# Input.net
KiCad netlist of a schematic drawn in Altium Designer
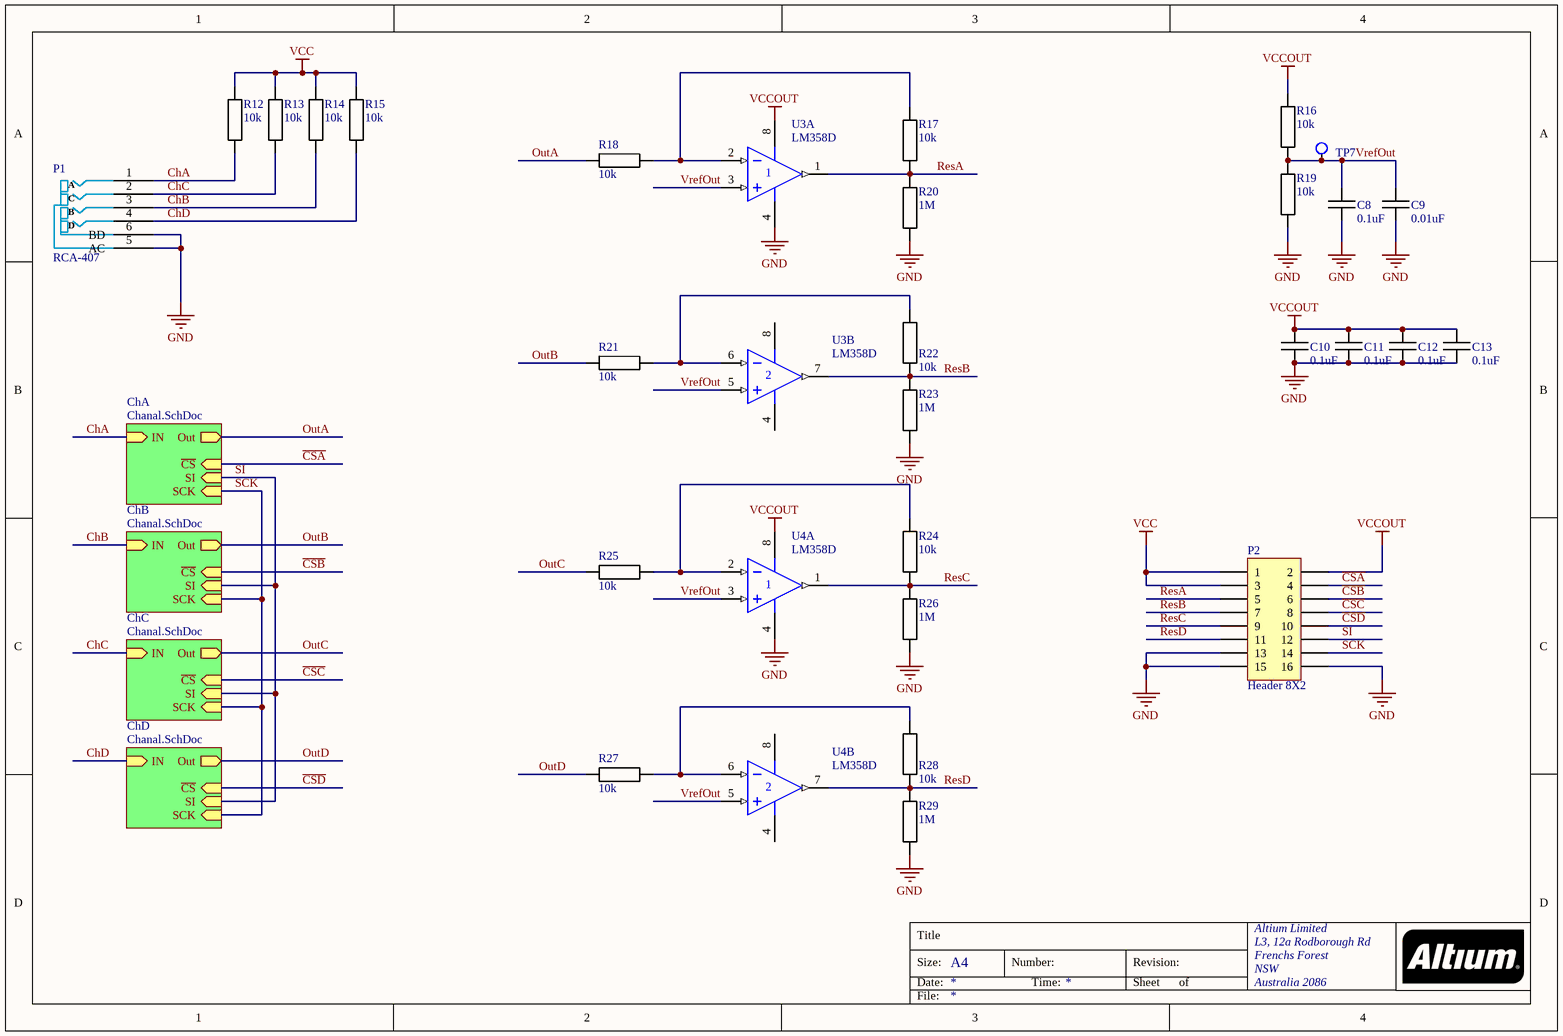
[diagram p0: Input.SchDoc]

(export (version "E")
  (design (tool "Eeschema 10.0.6"))
  (components
    (comp (ref "C8") (value "0.1uF") (footprint "SMD 0603") (libsource (lib "Maks_lib") (part "Capasitor")))
    (comp (ref "C9") (value "0.01uF") (footprint "SMD 0603") (libsource (lib "Maks_lib") (part "Capasitor")))
    (comp (ref "C10") (value "0.1uF") (footprint "SMD 0603") (libsource (lib "Maks_lib") (part "Capasitor")))
    (comp (ref "C11") (value "0.1uF") (footprint "SMD 0603") (libsource (lib "Maks_lib") (part "Capasitor")))
    (comp (ref "C12") (value "0.1uF") (footprint "SMD 0603") (libsource (lib "Maks_lib") (part "Capasitor")))
    (comp (ref "C13") (value "0.1uF") (footprint "SMD 0603") (libsource (lib "Maks_lib") (part "Capasitor")))
    (comp (ref "P1")
      (value "RCA-407")
      (footprint "RCA4")
      (description "RCA 2x2")
      (libsource (lib "Maks_lib") (part "RCA-407"))
    )
    (comp (ref "P2")
      (value "Header 8X2")
      (footprint "HDR2X8")
      (description "Header, 8-Pin, Dual row")
      (fields (field (name "PUBLISHER") "Altium Limited"))
      (libsource (lib "Miscellaneous Connectors") (part "Header 8X2"))
    )
    (comp (ref "R12") (value "10k") (footprint "SMD 0603") (libsource (lib "Maks_lib") (part "Resistor")))
    (comp (ref "R13") (value "10k") (footprint "SMD 0603") (libsource (lib "Maks_lib") (part "Resistor")))
    (comp (ref "R14") (value "10k") (footprint "SMD 0603") (libsource (lib "Maks_lib") (part "Resistor")))
    (comp (ref "R15") (value "10k") (footprint "SMD 0603") (libsource (lib "Maks_lib") (part "Resistor")))
    (comp (ref "R16") (value "10k") (footprint "SMD 0603") (libsource (lib "Maks_lib") (part "Resistor")))
    (comp (ref "R17") (value "10k") (footprint "SMD 0603") (libsource (lib "Maks_lib") (part "Resistor")))
    (comp (ref "R18") (value "10k") (footprint "SMD 0603") (libsource (lib "Maks_lib") (part "Resistor")))
    (comp (ref "R19") (value "10k") (footprint "SMD 0603") (libsource (lib "Maks_lib") (part "Resistor")))
    (comp (ref "R20") (value "1M") (footprint "SMD 0603") (libsource (lib "Maks_lib") (part "Resistor")))
    (comp (ref "R21") (value "10k") (footprint "SMD 0603") (libsource (lib "Maks_lib") (part "Resistor")))
    (comp (ref "R22") (value "10k") (footprint "SMD 0603") (libsource (lib "Maks_lib") (part "Resistor")))
    (comp (ref "R23") (value "1M") (footprint "SMD 0603") (libsource (lib "Maks_lib") (part "Resistor")))
    (comp (ref "R24") (value "10k") (footprint "SMD 0603") (libsource (lib "Maks_lib") (part "Resistor")))
    (comp (ref "R25") (value "10k") (footprint "SMD 0603") (libsource (lib "Maks_lib") (part "Resistor")))
    (comp (ref "R26") (value "1M") (footprint "SMD 0603") (libsource (lib "Maks_lib") (part "Resistor")))
    (comp (ref "R27") (value "10k") (footprint "SMD 0603") (libsource (lib "Maks_lib") (part "Resistor")))
    (comp (ref "R28") (value "10k") (footprint "SMD 0603") (libsource (lib "Maks_lib") (part "Resistor")))
    (comp (ref "R29") (value "1M") (footprint "SMD 0603") (libsource (lib "Maks_lib") (part "Resistor")))
    (comp (ref "TP7")
      (value "testPoint")
      (footprint "TESTPOINT")
      (libsource (lib "Maks_lib") (part "TestPoint"))
    )
    (comp (ref "U3")
      (value "LM358D")
      (footprint "751-02_N")
      (description "Dual Low-Power Operational Amplifier")
      (fields (field (name "PUBLISHER") "Altium Limited"))
      (libsource (lib "Motorola Amplifier Operational Amplifier") (part "LM358D"))
    )
    (comp (ref "U4")
      (value "LM358D")
      (footprint "751-02_N")
      (description "Dual Low-Power Operational Amplifier")
      (fields (field (name "PUBLISHER") "Altium Limited"))
      (libsource (lib "Motorola Amplifier Operational Amplifier") (part "LM358D"))
    )
  )
  (nets
    (net (code "1") (name "/CSA") (class "Default")
      (node (ref "P2") (pin "4") (pinfunction "4_4") (pintype "passive"))
    )
    (net (code "2") (name "/CSB") (class "Default")
      (node (ref "P2") (pin "6") (pinfunction "6_6") (pintype "passive"))
    )
    (net (code "3") (name "/CSC") (class "Default")
      (node (ref "P2") (pin "8") (pinfunction "8_8") (pintype "passive"))
    )
    (net (code "4") (name "/CSD") (class "Default")
      (node (ref "P2") (pin "10") (pinfunction "10_10") (pintype "passive"))
    )
    (net (code "5") (name "/ChA") (class "Default")
      (node (ref "P1") (pin "1") (pinfunction "A_1") (pintype "passive"))
      (node (ref "R12") (pin "1") (pinfunction "1_1") (pintype "passive"))
    )
    (net (code "6") (name "/ChB") (class "Default")
      (node (ref "P1") (pin "3") (pinfunction "B_3") (pintype "passive"))
      (node (ref "R14") (pin "1") (pinfunction "1_1") (pintype "passive"))
    )
    (net (code "7") (name "/ChC") (class "Default")
      (node (ref "P1") (pin "2") (pinfunction "C_2") (pintype "passive"))
      (node (ref "R13") (pin "1") (pinfunction "1_1") (pintype "passive"))
    )
    (net (code "8") (name "/ChD") (class "Default")
      (node (ref "P1") (pin "4") (pinfunction "D_4") (pintype "passive"))
      (node (ref "R15") (pin "1") (pinfunction "1_1") (pintype "passive"))
    )
    (net (code "9") (name "/OutA") (class "Default")
      (node (ref "R18") (pin "2") (pinfunction "2_2") (pintype "passive"))
    )
    (net (code "10") (name "/OutB") (class "Default")
      (node (ref "R21") (pin "2") (pinfunction "2_2") (pintype "passive"))
    )
    (net (code "11") (name "/OutC") (class "Default")
      (node (ref "R25") (pin "2") (pinfunction "2_2") (pintype "passive"))
    )
    (net (code "12") (name "/OutD") (class "Default")
      (node (ref "R27") (pin "2") (pinfunction "2_2") (pintype "passive"))
    )
    (net (code "13") (name "/ResA") (class "Default")
      (node (ref "P2") (pin "5") (pinfunction "5_5") (pintype "passive"))
      (node (ref "R17") (pin "2") (pinfunction "2_2") (pintype "passive"))
      (node (ref "R20") (pin "1") (pinfunction "1_1") (pintype "passive"))
      (node (ref "U3") (pin "1") (pinfunction "OUT_1") (pintype "output"))
    )
    (net (code "14") (name "/ResB") (class "Default")
      (node (ref "P2") (pin "7") (pinfunction "7_7") (pintype "passive"))
      (node (ref "R22") (pin "2") (pinfunction "2_2") (pintype "passive"))
      (node (ref "R23") (pin "1") (pinfunction "1_1") (pintype "passive"))
      (node (ref "U3") (pin "7") (pinfunction "OUT_7") (pintype "output"))
    )
    (net (code "15") (name "/ResC") (class "Default")
      (node (ref "P2") (pin "9") (pinfunction "9_9") (pintype "passive"))
      (node (ref "R24") (pin "2") (pinfunction "2_2") (pintype "passive"))
      (node (ref "R26") (pin "1") (pinfunction "1_1") (pintype "passive"))
      (node (ref "U4") (pin "1") (pinfunction "OUT_1") (pintype "output"))
    )
    (net (code "16") (name "/ResD") (class "Default")
      (node (ref "P2") (pin "11") (pinfunction "11_11") (pintype "passive"))
      (node (ref "R28") (pin "2") (pinfunction "2_2") (pintype "passive"))
      (node (ref "R29") (pin "1") (pinfunction "1_1") (pintype "passive"))
      (node (ref "U4") (pin "7") (pinfunction "OUT_7") (pintype "output"))
    )
    (net (code "17") (name "/SCK") (class "Default")
      (node (ref "P2") (pin "14") (pinfunction "14_14") (pintype "passive"))
    )
    (net (code "18") (name "/SI") (class "Default")
      (node (ref "P2") (pin "12") (pinfunction "12_12") (pintype "passive"))
    )
    (net (code "19") (name "/VrefOut") (class "Default")
      (node (ref "C8") (pin "1") (pinfunction "1_1") (pintype "passive"))
      (node (ref "C9") (pin "1") (pinfunction "1_1") (pintype "passive"))
      (node (ref "R16") (pin "1") (pinfunction "1_1") (pintype "passive"))
      (node (ref "R19") (pin "2") (pinfunction "2_2") (pintype "passive"))
      (node (ref "TP7") (pin "0") (pinfunction "0_0") (pintype "passive"))
      (node (ref "U3") (pin "3") (pinfunction "IN+_3") (pintype "input"))
      (node (ref "U3") (pin "5") (pinfunction "IN+_5") (pintype "input"))
      (node (ref "U4") (pin "3") (pinfunction "IN+_3") (pintype "input"))
      (node (ref "U4") (pin "5") (pinfunction "IN+_5") (pintype "input"))
    )
    (net (code "20") (name "GND") (class "Default")
      (node (ref "C10") (pin "2") (pinfunction "2_2") (pintype "passive"))
      (node (ref "C11") (pin "2") (pinfunction "2_2") (pintype "passive"))
      (node (ref "C12") (pin "2") (pinfunction "2_2") (pintype "passive"))
      (node (ref "C13") (pin "2") (pinfunction "2_2") (pintype "passive"))
      (node (ref "C8") (pin "2") (pinfunction "2_2") (pintype "passive"))
      (node (ref "C9") (pin "2") (pinfunction "2_2") (pintype "passive"))
      (node (ref "P1") (pin "5") (pinfunction "AC_5") (pintype "passive"))
      (node (ref "P1") (pin "6") (pinfunction "BD_6") (pintype "passive"))
      (node (ref "P2") (pin "13") (pinfunction "13_13") (pintype "passive"))
      (node (ref "P2") (pin "15") (pinfunction "15_15") (pintype "passive"))
      (node (ref "P2") (pin "16") (pinfunction "16_16") (pintype "passive"))
      (node (ref "R19") (pin "1") (pinfunction "1_1") (pintype "passive"))
      (node (ref "R20") (pin "2") (pinfunction "2_2") (pintype "passive"))
      (node (ref "R23") (pin "2") (pinfunction "2_2") (pintype "passive"))
      (node (ref "R26") (pin "2") (pinfunction "2_2") (pintype "passive"))
      (node (ref "R29") (pin "2") (pinfunction "2_2") (pintype "passive"))
      (node (ref "U3") (pin "4") (pinfunction "V-_4") (pintype "power_in"))
      (node (ref "U4") (pin "4") (pinfunction "V-_4") (pintype "power_in"))
    )
    (net (code "21") (name "Net-(U3A-IN-)") (class "Default")
      (node (ref "R17") (pin "1") (pinfunction "1_1") (pintype "passive"))
      (node (ref "R18") (pin "1") (pinfunction "1_1") (pintype "passive"))
      (node (ref "U3") (pin "2") (pinfunction "IN-_2") (pintype "input"))
    )
    (net (code "22") (name "Net-(U3B-IN-)") (class "Default")
      (node (ref "R21") (pin "1") (pinfunction "1_1") (pintype "passive"))
      (node (ref "R22") (pin "1") (pinfunction "1_1") (pintype "passive"))
      (node (ref "U3") (pin "6") (pinfunction "IN-_6") (pintype "input"))
    )
    (net (code "23") (name "Net-(U4A-IN-)") (class "Default")
      (node (ref "R24") (pin "1") (pinfunction "1_1") (pintype "passive"))
      (node (ref "R25") (pin "1") (pinfunction "1_1") (pintype "passive"))
      (node (ref "U4") (pin "2") (pinfunction "IN-_2") (pintype "input"))
    )
    (net (code "24") (name "Net-(U4B-IN-)") (class "Default")
      (node (ref "R27") (pin "1") (pinfunction "1_1") (pintype "passive"))
      (node (ref "R28") (pin "1") (pinfunction "1_1") (pintype "passive"))
      (node (ref "U4") (pin "6") (pinfunction "IN-_6") (pintype "input"))
    )
    (net (code "25") (name "VCC") (class "Default")
      (node (ref "P2") (pin "1") (pinfunction "1_1") (pintype "passive"))
      (node (ref "P2") (pin "3") (pinfunction "3_3") (pintype "passive"))
      (node (ref "R12") (pin "2") (pinfunction "2_2") (pintype "passive"))
      (node (ref "R13") (pin "2") (pinfunction "2_2") (pintype "passive"))
      (node (ref "R14") (pin "2") (pinfunction "2_2") (pintype "passive"))
      (node (ref "R15") (pin "2") (pinfunction "2_2") (pintype "passive"))
    )
    (net (code "26") (name "VCCOUT") (class "Default")
      (node (ref "C10") (pin "1") (pinfunction "1_1") (pintype "passive"))
      (node (ref "C11") (pin "1") (pinfunction "1_1") (pintype "passive"))
      (node (ref "C12") (pin "1") (pinfunction "1_1") (pintype "passive"))
      (node (ref "C13") (pin "1") (pinfunction "1_1") (pintype "passive"))
      (node (ref "P2") (pin "2") (pinfunction "2_2") (pintype "passive"))
      (node (ref "R16") (pin "2") (pinfunction "2_2") (pintype "passive"))
      (node (ref "U3") (pin "8") (pinfunction "V+_8") (pintype "power_in"))
      (node (ref "U4") (pin "8") (pinfunction "V+_8") (pintype "power_in"))
    )
    (net (code "27") (name "unconnected-(U3B-V+-Pad8)") (class "Default")
      (node (ref "U3") (pin "8") (pinfunction "V+_8") (pintype "power_in"))
    )
    (net (code "28") (name "unconnected-(U3B-V--Pad4)") (class "Default")
      (node (ref "U3") (pin "4") (pinfunction "V-_4") (pintype "power_in"))
    )
    (net (code "29") (name "unconnected-(U4B-V+-Pad8)") (class "Default")
      (node (ref "U4") (pin "8") (pinfunction "V+_8") (pintype "power_in"))
    )
    (net (code "30") (name "unconnected-(U4B-V--Pad4)") (class "Default")
      (node (ref "U4") (pin "4") (pinfunction "V-_4") (pintype "power_in"))
    )
  )
)
